# STM32_Schematic.net
KiCad netlist of a schematic drawn in Altium Designer
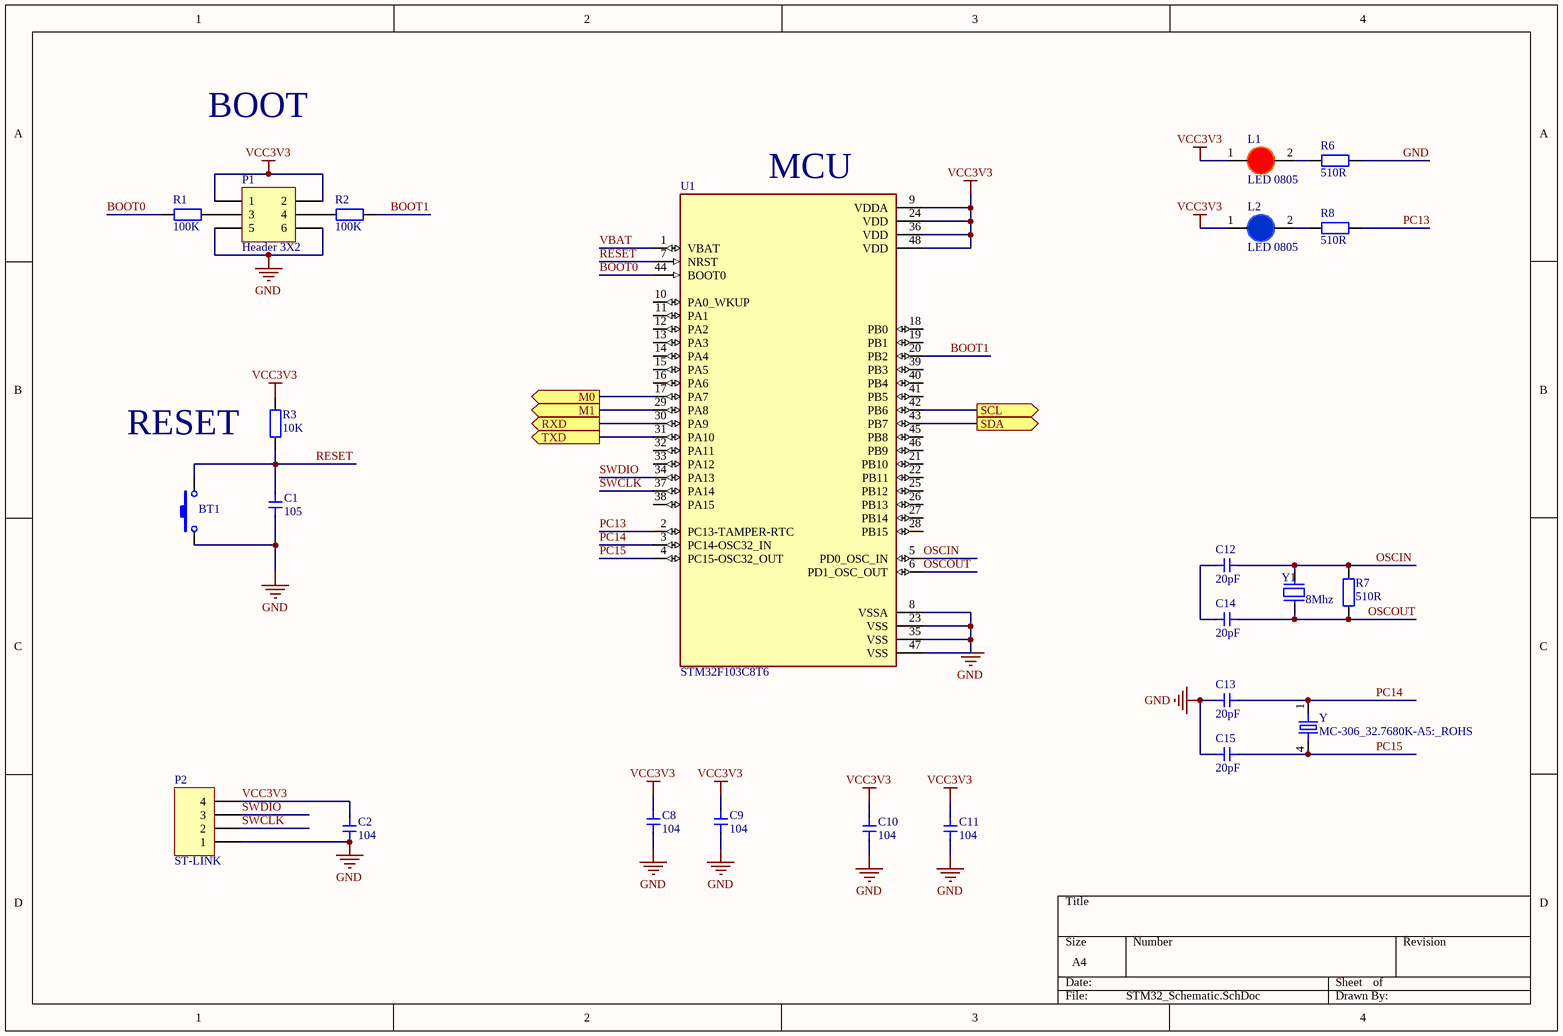
[diagram p0: STM32_Schematic.SchDoc]

(export (version "E")
  (design (tool "Eeschema 10.0.6"))
  (components
    (comp (ref "BT1")
      (value "Nut Nhan 2 Chan SMD 3x6x2.5")
      (footprint "Nut Nhan 2 Chan SMD 3x6x2.5")
      (libsource (lib "Altium_Lib_by_KhueNguyenCreator") (part "Nut Nhan 2 Chan SMD 3x6x2.5"))
    )
    (comp (ref "C1")
      (value "105")
      (footprint "Cap 0805")
      (description "Capacitor SMD 0805")
      (libsource (lib "Altium_Lib_by_KhueNguyenCreator") (part "Cap 0805"))
    )
    (comp (ref "C2")
      (value "104")
      (footprint "Cap 0805")
      (description "Capacitor SMD 0805")
      (libsource (lib "Altium_Lib_by_KhueNguyenCreator") (part "Cap 0805"))
    )
    (comp (ref "C8")
      (value "104")
      (footprint "Cap 0805")
      (description "Capacitor SMD 0805")
      (libsource (lib "Altium_Lib_by_KhueNguyenCreator") (part "Cap 0805"))
    )
    (comp (ref "C9")
      (value "104")
      (footprint "Cap 0805")
      (description "Capacitor SMD 0805")
      (libsource (lib "Altium_Lib_by_KhueNguyenCreator") (part "Cap 0805"))
    )
    (comp (ref "C10")
      (value "104")
      (footprint "Cap 0805")
      (description "Capacitor SMD 0805")
      (libsource (lib "Altium_Lib_by_KhueNguyenCreator") (part "Cap 0805"))
    )
    (comp (ref "C11")
      (value "104")
      (footprint "Cap 0805")
      (description "Capacitor SMD 0805")
      (libsource (lib "Altium_Lib_by_KhueNguyenCreator") (part "Cap 0805"))
    )
    (comp (ref "C12")
      (value "20pF")
      (footprint "Cap 0805")
      (description "Capacitor SMD 0805")
      (libsource (lib "Altium_Lib_by_KhueNguyenCreator") (part "Cap 0805"))
    )
    (comp (ref "C13")
      (value "20pF")
      (footprint "Cap 0805")
      (description "Capacitor SMD 0805")
      (libsource (lib "Altium_Lib_by_KhueNguyenCreator") (part "Cap 0805"))
    )
    (comp (ref "C14")
      (value "20pF")
      (footprint "Cap 0805")
      (description "Capacitor SMD 0805")
      (libsource (lib "Altium_Lib_by_KhueNguyenCreator") (part "Cap 0805"))
    )
    (comp (ref "C15")
      (value "20pF")
      (footprint "Cap 0805")
      (description "Capacitor SMD 0805")
      (libsource (lib "Altium_Lib_by_KhueNguyenCreator") (part "Cap 0805"))
    )
    (comp (ref "L1")
      (value "LED 0805")
      (footprint "LED-0805-Red")
      (description "Dán")
      (libsource (lib "Altium_Lib_by_KhueNguyenCreator") (part "LED 0805 Do"))
    )
    (comp (ref "L2")
      (value "LED 0805")
      (footprint "LED-0805-Blue")
      (description "Dán")
      (libsource (lib "Altium_Lib_by_KhueNguyenCreator") (part "LED 0805 Xanh Duong"))
    )
    (comp (ref "P1")
      (value "Header 3X2")
      (footprint "HDR2X3")
      (description "Header, 3-Pin, Dual row")
      (fields (field (name "PUBLISHER") "Altium Limited"))
      (libsource (lib "Miscellaneous Connectors") (part "Header 3X2"))
    )
    (comp (ref "P2")
      (value "ST-LINK")
      (footprint "HDR1X4")
      (description "Header, 4-Pin")
      (fields (field (name "PUBLISHER") "Altium Limited"))
      (libsource (lib "Miscellaneous Connectors") (part "Header 4"))
    )
    (comp (ref "R1")
      (value "100K")
      (footprint "tro smd 0805")
      (description "Dán")
      (libsource (lib "THU VIEN SCH") (part "Tro 0805 1% 0.5R"))
    )
    (comp (ref "R2")
      (value "100K")
      (footprint "tro smd 0805")
      (description "Dán")
      (libsource (lib "THU VIEN SCH") (part "Tro 0805 1% 0.5R"))
    )
    (comp (ref "R3")
      (value "10K")
      (footprint "tro smd 0805")
      (description "Dán")
      (libsource (lib "THU VIEN SCH") (part "Tro 0805 1% 0.5R"))
    )
    (comp (ref "R6")
      (value "510R")
      (footprint "tro smd 0805")
      (description "Dán")
      (libsource (lib "THU VIEN SCH") (part "Tro 0805 1% 0.5R"))
    )
    (comp (ref "R7")
      (value "510R")
      (footprint "tro smd 0805")
      (description "Dán")
      (libsource (lib "THU VIEN SCH") (part "Tro 0805 1% 0.5R"))
    )
    (comp (ref "R8")
      (value "510R")
      (footprint "tro smd 0805")
      (description "Dán")
      (libsource (lib "THU VIEN SCH") (part "Tro 0805 1% 0.5R"))
    )
    (comp (ref "U1")
      (value "STM32F103C8T6")
      (footprint "QFP50P900X900X160-48N")
      (description "ARM® Cortex®-M3 STM32F1 Microcontroller IC 32-Bit 72MHz 64KB (64K x 8) FLASH 48-LQFP (7x7)")
      (fields (field (name "MF") "STMicroelectronics"))
      (libsource (lib "STM32F103C8T6") (part "STM32F103C8T6"))
    )
    (comp (ref "Y")
      (value "MC-306_32.7680K-A5:_ROHS")
      (footprint "OSCL550P800X320X254-4N")
      (description "32.768kHz Â±100ppm Crystal 12.5pF 50 kOhms 4-SOJ, 5.50mm pitch")
      (fields (field (name "MP") "MC-306 32.7680K-A5: ROHS") (field (name "MF") "EPSON"))
      (libsource (lib "MC-306_32.7680K-A5__ROHS") (part "MC-306_32.7680K-A5{colon}_ROHS"))
    )
    (comp (ref "Y1")
      (value "8Mhz")
      (footprint "Thach Anh 2 chan SMD5032")
      (description "Crystal For all Crystal 2pin.")
      (libsource (lib "Altium_Lib_by_KhueNguyenCreator") (part "Thach Anh 2 chan SMD 5032"))
    )
  )
  (nets
    (net (code "1") (name "/BOOT0") (class "Default")
      (node (ref "R1") (pin "2") (pinfunction "2_2") (pintype "passive"))
      (node (ref "U1") (pin "44") (pinfunction "BOOT0_44") (pintype "input"))
    )
    (net (code "2") (name "/BOOT1") (class "Default")
      (node (ref "R2") (pin "1") (pinfunction "1_1") (pintype "passive"))
      (node (ref "U1") (pin "20") (pinfunction "PB2_20") (pintype "bidirectional"))
    )
    (net (code "3") (name "/M0") (class "Default")
      (node (ref "U1") (pin "17") (pinfunction "PA7_17") (pintype "bidirectional"))
    )
    (net (code "4") (name "/M1") (class "Default")
      (node (ref "U1") (pin "29") (pinfunction "PA8_29") (pintype "bidirectional"))
    )
    (net (code "5") (name "/OSCIN") (class "Default")
      (node (ref "C12") (pin "1") (pinfunction "1_1") (pintype "passive"))
      (node (ref "R7") (pin "2") (pinfunction "2_2") (pintype "passive"))
      (node (ref "U1") (pin "5") (pinfunction "PD0_OSC_IN_5") (pintype "bidirectional"))
      (node (ref "Y1") (pin "1") (pinfunction "1_1") (pintype "passive"))
    )
    (net (code "6") (name "/OSCOUT") (class "Default")
      (node (ref "C14") (pin "1") (pinfunction "1_1") (pintype "passive"))
      (node (ref "R7") (pin "1") (pinfunction "1_1") (pintype "passive"))
      (node (ref "U1") (pin "6") (pinfunction "PD1_OSC_OUT_6") (pintype "bidirectional"))
      (node (ref "Y1") (pin "2") (pinfunction "2_2") (pintype "passive"))
    )
    (net (code "7") (name "/PC13") (class "Default")
      (node (ref "R8") (pin "2") (pinfunction "2_2") (pintype "passive"))
      (node (ref "U1") (pin "2") (pinfunction "PC13-TAMPER-RTC_2") (pintype "bidirectional"))
    )
    (net (code "8") (name "/PC14") (class "Default")
      (node (ref "C13") (pin "1") (pinfunction "1_1") (pintype "passive"))
      (node (ref "U1") (pin "3") (pinfunction "PC14-OSC32_IN_3") (pintype "bidirectional"))
      (node (ref "Y") (pin "1") (pinfunction "1_1") (pintype "passive"))
    )
    (net (code "9") (name "/PC15") (class "Default")
      (node (ref "C15") (pin "1") (pinfunction "1_1") (pintype "passive"))
      (node (ref "U1") (pin "4") (pinfunction "PC15-OSC32_OUT_4") (pintype "bidirectional"))
      (node (ref "Y") (pin "4") (pinfunction "4_4") (pintype "passive"))
    )
    (net (code "10") (name "/RESET") (class "Default")
      (node (ref "BT1") (pin "2") (pinfunction "2_2") (pintype "passive"))
      (node (ref "C1") (pin "2") (pinfunction "2_2") (pintype "passive"))
      (node (ref "R3") (pin "1") (pinfunction "1_1") (pintype "passive"))
      (node (ref "U1") (pin "7") (pinfunction "NRST_7") (pintype "input"))
    )
    (net (code "11") (name "/RXD") (class "Default")
      (node (ref "U1") (pin "30") (pinfunction "PA9_30") (pintype "bidirectional"))
    )
    (net (code "12") (name "/SCL") (class "Default")
      (node (ref "U1") (pin "42") (pinfunction "PB6_42") (pintype "bidirectional"))
    )
    (net (code "13") (name "/SDA") (class "Default")
      (node (ref "U1") (pin "43") (pinfunction "PB7_43") (pintype "bidirectional"))
    )
    (net (code "14") (name "/SWCLK") (class "Default")
      (node (ref "P2") (pin "2") (pinfunction "2_2") (pintype "passive"))
      (node (ref "U1") (pin "37") (pinfunction "PA14_37") (pintype "bidirectional"))
    )
    (net (code "15") (name "/SWDIO") (class "Default")
      (node (ref "P2") (pin "3") (pinfunction "3_3") (pintype "passive"))
      (node (ref "U1") (pin "34") (pinfunction "PA13_34") (pintype "bidirectional"))
    )
    (net (code "16") (name "/TXD") (class "Default")
      (node (ref "U1") (pin "31") (pinfunction "PA10_31") (pintype "bidirectional"))
    )
    (net (code "17") (name "/VBAT") (class "Default")
      (node (ref "U1") (pin "1") (pinfunction "VBAT_1") (pintype "bidirectional"))
    )
    (net (code "18") (name "GND") (class "Default")
      (node (ref "BT1") (pin "1") (pinfunction "1_1") (pintype "passive"))
      (node (ref "C1") (pin "1") (pinfunction "1_1") (pintype "passive"))
      (node (ref "C10") (pin "1") (pinfunction "1_1") (pintype "passive"))
      (node (ref "C11") (pin "1") (pinfunction "1_1") (pintype "passive"))
      (node (ref "C13") (pin "2") (pinfunction "2_2") (pintype "passive"))
      (node (ref "C15") (pin "2") (pinfunction "2_2") (pintype "passive"))
      (node (ref "C2") (pin "1") (pinfunction "1_1") (pintype "passive"))
      (node (ref "C8") (pin "1") (pinfunction "1_1") (pintype "passive"))
      (node (ref "C9") (pin "1") (pinfunction "1_1") (pintype "passive"))
      (node (ref "P1") (pin "5") (pinfunction "5_5") (pintype "passive"))
      (node (ref "P1") (pin "6") (pinfunction "6_6") (pintype "passive"))
      (node (ref "P2") (pin "1") (pinfunction "1_1") (pintype "passive"))
      (node (ref "R6") (pin "2") (pinfunction "2_2") (pintype "passive"))
      (node (ref "U1") (pin "23") (pinfunction "VSS_23") (pintype "power_in"))
      (node (ref "U1") (pin "35") (pinfunction "VSS_35") (pintype "power_in"))
      (node (ref "U1") (pin "47") (pinfunction "VSS_47") (pintype "power_in"))
      (node (ref "U1") (pin "8") (pinfunction "VSSA_8") (pintype "power_in"))
    )
    (net (code "19") (name "Net-(C12-Pad2)") (class "Default")
      (node (ref "C12") (pin "2") (pinfunction "2_2") (pintype "passive"))
      (node (ref "C14") (pin "2") (pinfunction "2_2") (pintype "passive"))
    )
    (net (code "20") (name "Net-(L1-K)") (class "Default")
      (node (ref "L1") (pin "2") (pinfunction "K_2") (pintype "passive"))
      (node (ref "R6") (pin "1") (pinfunction "1_1") (pintype "passive"))
    )
    (net (code "21") (name "Net-(L2-K)") (class "Default")
      (node (ref "L2") (pin "2") (pinfunction "K_2") (pintype "passive"))
      (node (ref "R8") (pin "1") (pinfunction "1_1") (pintype "passive"))
    )
    (net (code "22") (name "Net-(P1-Pad3)") (class "Default")
      (node (ref "P1") (pin "3") (pinfunction "3_3") (pintype "passive"))
      (node (ref "R1") (pin "1") (pinfunction "1_1") (pintype "passive"))
    )
    (net (code "23") (name "Net-(P1-Pad4)") (class "Default")
      (node (ref "P1") (pin "4") (pinfunction "4_4") (pintype "passive"))
      (node (ref "R2") (pin "2") (pinfunction "2_2") (pintype "passive"))
    )
    (net (code "24") (name "VCC3V3") (class "Default")
      (node (ref "C10") (pin "2") (pinfunction "2_2") (pintype "passive"))
      (node (ref "C11") (pin "2") (pinfunction "2_2") (pintype "passive"))
      (node (ref "C2") (pin "2") (pinfunction "2_2") (pintype "passive"))
      (node (ref "C8") (pin "2") (pinfunction "2_2") (pintype "passive"))
      (node (ref "C9") (pin "2") (pinfunction "2_2") (pintype "passive"))
      (node (ref "L1") (pin "1") (pinfunction "A_1") (pintype "passive"))
      (node (ref "L2") (pin "1") (pinfunction "A_1") (pintype "passive"))
      (node (ref "P1") (pin "1") (pinfunction "1_1") (pintype "passive"))
      (node (ref "P1") (pin "2") (pinfunction "2_2") (pintype "passive"))
      (node (ref "P2") (pin "4") (pinfunction "4_4") (pintype "passive"))
      (node (ref "R3") (pin "2") (pinfunction "2_2") (pintype "passive"))
      (node (ref "U1") (pin "24") (pinfunction "VDD_24") (pintype "power_in"))
      (node (ref "U1") (pin "36") (pinfunction "VDD_36") (pintype "power_in"))
      (node (ref "U1") (pin "48") (pinfunction "VDD_48") (pintype "power_in"))
      (node (ref "U1") (pin "9") (pinfunction "VDDA_9") (pintype "power_in"))
    )
    (net (code "25") (name "unconnected-(U1-PA0_WKUP-Pad10)") (class "Default")
      (node (ref "U1") (pin "10") (pinfunction "PA0_WKUP_10") (pintype "bidirectional"))
    )
    (net (code "26") (name "unconnected-(U1-PA1-Pad11)") (class "Default")
      (node (ref "U1") (pin "11") (pinfunction "PA1_11") (pintype "bidirectional"))
    )
    (net (code "27") (name "unconnected-(U1-PA2-Pad12)") (class "Default")
      (node (ref "U1") (pin "12") (pinfunction "PA2_12") (pintype "bidirectional"))
    )
    (net (code "28") (name "unconnected-(U1-PA3-Pad13)") (class "Default")
      (node (ref "U1") (pin "13") (pinfunction "PA3_13") (pintype "bidirectional"))
    )
    (net (code "29") (name "unconnected-(U1-PA4-Pad14)") (class "Default")
      (node (ref "U1") (pin "14") (pinfunction "PA4_14") (pintype "bidirectional"))
    )
    (net (code "30") (name "unconnected-(U1-PA5-Pad15)") (class "Default")
      (node (ref "U1") (pin "15") (pinfunction "PA5_15") (pintype "bidirectional"))
    )
    (net (code "31") (name "unconnected-(U1-PA6-Pad16)") (class "Default")
      (node (ref "U1") (pin "16") (pinfunction "PA6_16") (pintype "bidirectional"))
    )
    (net (code "32") (name "unconnected-(U1-PA11-Pad32)") (class "Default")
      (node (ref "U1") (pin "32") (pinfunction "PA11_32") (pintype "bidirectional"))
    )
    (net (code "33") (name "unconnected-(U1-PA12-Pad33)") (class "Default")
      (node (ref "U1") (pin "33") (pinfunction "PA12_33") (pintype "bidirectional"))
    )
    (net (code "34") (name "unconnected-(U1-PA15-Pad38)") (class "Default")
      (node (ref "U1") (pin "38") (pinfunction "PA15_38") (pintype "bidirectional"))
    )
    (net (code "35") (name "unconnected-(U1-PB0-Pad18)") (class "Default")
      (node (ref "U1") (pin "18") (pinfunction "PB0_18") (pintype "bidirectional"))
    )
    (net (code "36") (name "unconnected-(U1-PB1-Pad19)") (class "Default")
      (node (ref "U1") (pin "19") (pinfunction "PB1_19") (pintype "bidirectional"))
    )
    (net (code "37") (name "unconnected-(U1-PB3-Pad39)") (class "Default")
      (node (ref "U1") (pin "39") (pinfunction "PB3_39") (pintype "bidirectional"))
    )
    (net (code "38") (name "unconnected-(U1-PB4-Pad40)") (class "Default")
      (node (ref "U1") (pin "40") (pinfunction "PB4_40") (pintype "bidirectional"))
    )
    (net (code "39") (name "unconnected-(U1-PB5-Pad41)") (class "Default")
      (node (ref "U1") (pin "41") (pinfunction "PB5_41") (pintype "bidirectional"))
    )
    (net (code "40") (name "unconnected-(U1-PB8-Pad45)") (class "Default")
      (node (ref "U1") (pin "45") (pinfunction "PB8_45") (pintype "bidirectional"))
    )
    (net (code "41") (name "unconnected-(U1-PB9-Pad46)") (class "Default")
      (node (ref "U1") (pin "46") (pinfunction "PB9_46") (pintype "bidirectional"))
    )
    (net (code "42") (name "unconnected-(U1-PB10-Pad21)") (class "Default")
      (node (ref "U1") (pin "21") (pinfunction "PB10_21") (pintype "bidirectional"))
    )
    (net (code "43") (name "unconnected-(U1-PB11-Pad22)") (class "Default")
      (node (ref "U1") (pin "22") (pinfunction "PB11_22") (pintype "bidirectional"))
    )
    (net (code "44") (name "unconnected-(U1-PB12-Pad25)") (class "Default")
      (node (ref "U1") (pin "25") (pinfunction "PB12_25") (pintype "bidirectional"))
    )
    (net (code "45") (name "unconnected-(U1-PB13-Pad26)") (class "Default")
      (node (ref "U1") (pin "26") (pinfunction "PB13_26") (pintype "bidirectional"))
    )
    (net (code "46") (name "unconnected-(U1-PB14-Pad27)") (class "Default")
      (node (ref "U1") (pin "27") (pinfunction "PB14_27") (pintype "bidirectional"))
    )
    (net (code "47") (name "unconnected-(U1-PB15-Pad28)") (class "Default")
      (node (ref "U1") (pin "28") (pinfunction "PB15_28") (pintype "bidirectional"))
    )
  )
)
